# Sheet1.net
KiCad netlist of a schematic drawn in Altium Designer
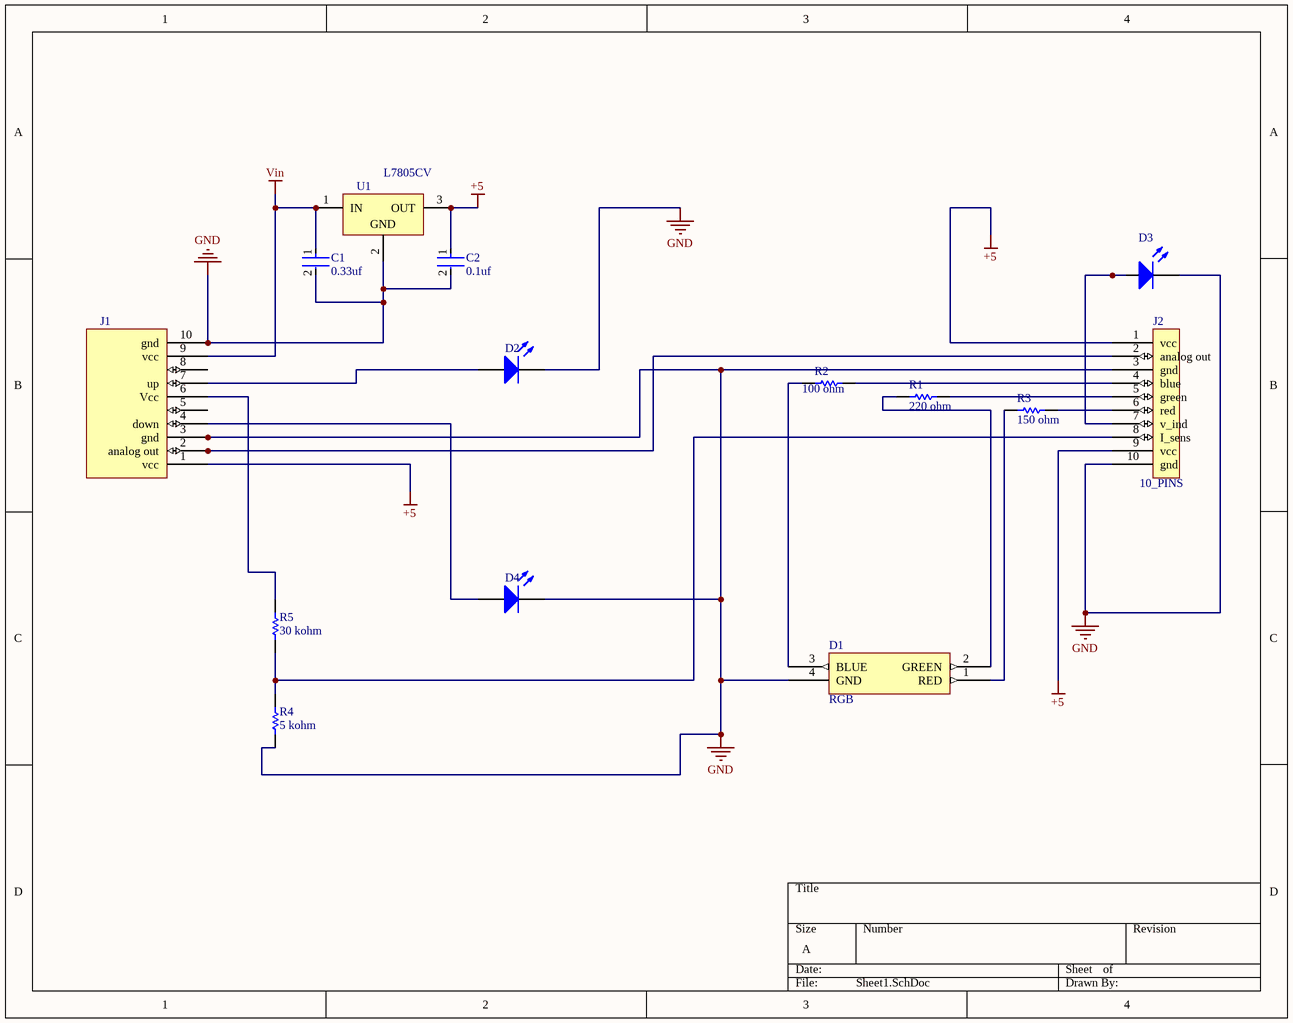
[diagram p0: Sheet1.SchDoc]

(export (version "E")
  (design (tool "Eeschema 10.0.6"))
  (components
    (comp (ref "C1")
      (value "0.33uf")
      (footprint "FP-K15H5-MFG")
      (description "CAP CER 0.1UF 50V X7R RADIAL")
      (fields (field (name "TOLERANCE") "10%") (field (name "VOLTAGE") "50V"))
      (libsource (lib "Altium Content Vault") (part "02cd4be3c70576c341d710602a673aa"))
    )
    (comp (ref "C2")
      (value "0.1uf")
      (footprint "FP-K15H5-MFG")
      (description "CAP CER 0.1UF 50V X7R RADIAL")
      (fields (field (name "TOLERANCE") "10%") (field (name "VOLTAGE") "50V"))
      (libsource (lib "Altium Content Vault") (part "02cd4be3c70576c341d710602a673aa"))
    )
    (comp (ref "D1") (value "RGB") (footprint "RGB LED") (libsource (lib "*") (part "RGB LED")))
    (comp (ref "D2")
      (value "Light-Emitting Diode")
      (footprint "LED")
      (libsource (lib "Simulation Generic Components") (part "LED"))
    )
    (comp (ref "D3")
      (value "Light-Emitting Diode")
      (footprint "LED")
      (libsource (lib "Simulation Generic Components") (part "LED"))
    )
    (comp (ref "D4")
      (value "Light-Emitting Diode")
      (footprint "LED")
      (libsource (lib "Simulation Generic Components") (part "LED"))
    )
    (comp (ref "J1") (value "~") (footprint "pin_10") (libsource (lib "*") (part "pin_1")))
    (comp (ref "J2") (value "10_PINS") (footprint "pin_10") (libsource (lib "*") (part "PIN_2")))
    (comp (ref "R1")
      (value "220 ohm")
      (footprint "RESISTANCE")
      (description "Resistor")
      (libsource (lib "Simulation Generic Components") (part "Resistor"))
    )
    (comp (ref "R2")
      (value "100 ohm")
      (footprint "RESISTANCE")
      (description "Resistor")
      (libsource (lib "Simulation Generic Components") (part "Resistor"))
    )
    (comp (ref "R3")
      (value "150 ohm")
      (footprint "RESISTANCE")
      (description "Resistor")
      (libsource (lib "Simulation Generic Components") (part "Resistor"))
    )
    (comp (ref "R4")
      (value "5 kohm")
      (footprint "RESISTANCE")
      (description "Resistor")
      (libsource (lib "Simulation Generic Components") (part "Resistor"))
    )
    (comp (ref "R5")
      (value "30 kohm")
      (footprint "RESISTANCE")
      (description "Resistor")
      (libsource (lib "Simulation Generic Components") (part "Resistor"))
    )
    (comp (ref "U1")
      (value "L7805CV")
      (footprint "TO220")
      (description "Positive Voltage Regulator, 5V, 3-Pin TO-220")
      (libsource (lib "Altium Content Vault") (part "PM-REG-L4940-SIL3"))
    )
  )
  (nets
    (net (code "1") (name "+5") (class "Default")
      (node (ref "C2") (pin "1") (pinfunction "1_1") (pintype "passive"))
      (node (ref "J1") (pin "1") (pinfunction "vcc_1") (pintype "power_in"))
      (node (ref "J2") (pin "1") (pinfunction "vcc_1") (pintype "power_in"))
      (node (ref "J2") (pin "9") (pinfunction "vcc_9") (pintype "power_in"))
      (node (ref "U1") (pin "3") (pinfunction "OUT_3") (pintype "power_in"))
    )
    (net (code "2") (name "GND") (class "Default")
      (node (ref "C1") (pin "2") (pinfunction "2_2") (pintype "passive"))
      (node (ref "C2") (pin "2") (pinfunction "2_2") (pintype "passive"))
      (node (ref "D1") (pin "4") (pinfunction "GND_4") (pintype "power_in"))
      (node (ref "D2") (pin "2") (pinfunction "K_2") (pintype "passive"))
      (node (ref "D3") (pin "2") (pinfunction "K_2") (pintype "passive"))
      (node (ref "D4") (pin "2") (pinfunction "K_2") (pintype "passive"))
      (node (ref "J1") (pin "10") (pinfunction "gnd_10") (pintype "power_in"))
      (node (ref "J1") (pin "3") (pinfunction "gnd_3") (pintype "power_in"))
      (node (ref "J2") (pin "10") (pinfunction "gnd_10") (pintype "power_in"))
      (node (ref "J2") (pin "3") (pinfunction "gnd_3") (pintype "power_in"))
      (node (ref "R4") (pin "2") (pinfunction "2_2") (pintype "passive"))
      (node (ref "U1") (pin "2") (pinfunction "GND_2") (pintype "power_in"))
    )
    (net (code "3") (name "Net-(D1-BLUE)") (class "Default")
      (node (ref "D1") (pin "3") (pinfunction "BLUE_3") (pintype "output"))
      (node (ref "R2") (pin "2") (pinfunction "2_2") (pintype "passive"))
    )
    (net (code "4") (name "Net-(D1-GREEN)") (class "Default")
      (node (ref "D1") (pin "2") (pinfunction "GREEN_2") (pintype "output"))
      (node (ref "R1") (pin "2") (pinfunction "2_2") (pintype "passive"))
    )
    (net (code "5") (name "Net-(D1-RED)") (class "Default")
      (node (ref "D1") (pin "1") (pinfunction "RED_1") (pintype "output"))
      (node (ref "R3") (pin "2") (pinfunction "2_2") (pintype "passive"))
    )
    (net (code "6") (name "Net-(D2-A)") (class "Default")
      (node (ref "D2") (pin "1") (pinfunction "A_1") (pintype "passive"))
      (node (ref "J1") (pin "7") (pinfunction "up_7") (pintype "bidirectional"))
    )
    (net (code "7") (name "Net-(D3-A)") (class "Default")
      (node (ref "D3") (pin "1") (pinfunction "A_1") (pintype "passive"))
      (node (ref "J2") (pin "7") (pinfunction "v_ind_7") (pintype "bidirectional"))
    )
    (net (code "8") (name "Net-(D4-A)") (class "Default")
      (node (ref "D4") (pin "1") (pinfunction "A_1") (pintype "passive"))
      (node (ref "J1") (pin "4") (pinfunction "down_4") (pintype "bidirectional"))
    )
    (net (code "9") (name "Net-(J1-Vcc)") (class "Default")
      (node (ref "J1") (pin "6") (pinfunction "Vcc_6") (pintype "power_in"))
      (node (ref "R5") (pin "1") (pinfunction "1_1") (pintype "passive"))
    )
    (net (code "10") (name "Net-(J1-analog_out)") (class "Default")
      (node (ref "J1") (pin "2") (pinfunction "analog_out_2") (pintype "bidirectional"))
      (node (ref "J2") (pin "2") (pinfunction "analog_out_2") (pintype "bidirectional"))
    )
    (net (code "11") (name "Net-(J2-I_sens)") (class "Default")
      (node (ref "J2") (pin "8") (pinfunction "I_sens_8") (pintype "bidirectional"))
      (node (ref "R4") (pin "1") (pinfunction "1_1") (pintype "passive"))
      (node (ref "R5") (pin "2") (pinfunction "2_2") (pintype "passive"))
    )
    (net (code "12") (name "Net-(J2-blue)") (class "Default")
      (node (ref "J2") (pin "4") (pinfunction "blue_4") (pintype "bidirectional"))
      (node (ref "R2") (pin "1") (pinfunction "1_1") (pintype "passive"))
    )
    (net (code "13") (name "Net-(J2-green)") (class "Default")
      (node (ref "J2") (pin "5") (pinfunction "green_5") (pintype "bidirectional"))
      (node (ref "R1") (pin "1") (pinfunction "1_1") (pintype "passive"))
    )
    (net (code "14") (name "Net-(J2-red)") (class "Default")
      (node (ref "J2") (pin "6") (pinfunction "red_6") (pintype "bidirectional"))
      (node (ref "R3") (pin "1") (pinfunction "1_1") (pintype "passive"))
    )
    (net (code "15") (name "Vin") (class "Default")
      (node (ref "C1") (pin "1") (pinfunction "1_1") (pintype "passive"))
      (node (ref "J1") (pin "9") (pinfunction "vcc_9") (pintype "power_in"))
      (node (ref "U1") (pin "1") (pinfunction "IN_1") (pintype "power_in"))
    )
    (net (code "16") (name "unconnected-(J1-Pad5)") (class "Default")
      (node (ref "J1") (pin "5") (pintype "bidirectional"))
    )
    (net (code "17") (name "unconnected-(J1-Pad8)") (class "Default")
      (node (ref "J1") (pin "8") (pintype "bidirectional"))
    )
  )
)
